# CDC_Amp_v31.net
KiCad netlist of a schematic drawn in EAGLE
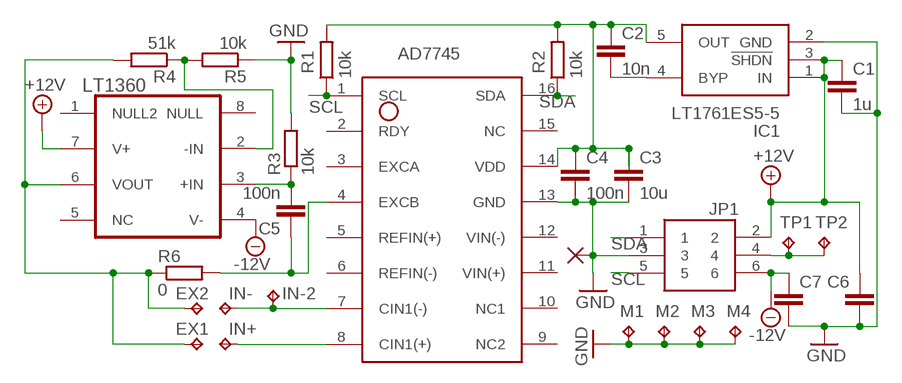
[diagram p0: schematic, sheet 1]

(export (version "E")
  (design (tool "Eeschema 10.0.6"))
  (components
    (comp (ref "AD7745")
      (value "AD7745")
      (footprint "eagle-import:AD7745_TSSOP_16")
      (libsource (lib "eagle-import") (part "AD7745_TSSOP_16"))
    )
    (comp (ref "C1")
      (value "1u")
      (footprint "eagle-import:RCL_C0805")
      (libsource (lib "eagle-import") (part "RCL_C-EUC0805"))
    )
    (comp (ref "C2")
      (value "10n")
      (footprint "eagle-import:RCL_C0805")
      (libsource (lib "eagle-import") (part "RCL_C-EUC0805"))
    )
    (comp (ref "C3")
      (value "10u")
      (footprint "eagle-import:RCL_C0805")
      (libsource (lib "eagle-import") (part "RCL_C-EUC0805"))
    )
    (comp (ref "C4")
      (value "100n")
      (footprint "eagle-import:RCL_C0805")
      (libsource (lib "eagle-import") (part "RCL_C-EUC0805"))
    )
    (comp (ref "C5")
      (value "100n")
      (footprint "eagle-import:RCL_C0805")
      (libsource (lib "eagle-import") (part "RCL_C-EUC0805"))
    )
    (comp (ref "C6")
      (value "RCL_C-EUC1206")
      (footprint "eagle-import:RCL_C1206")
      (libsource (lib "eagle-import") (part "RCL_C-EUC1206"))
    )
    (comp (ref "C7")
      (value "RCL_C-EUC1206")
      (footprint "eagle-import:RCL_C1206")
      (libsource (lib "eagle-import") (part "RCL_C-EUC1206"))
    )
    (comp (ref "EX1")
      (value "TESTPAD_TPTP15R")
      (footprint "eagle-import:TESTPAD_TP15R")
      (libsource (lib "eagle-import") (part "TESTPAD_TPTP15R"))
    )
    (comp (ref "EX2")
      (value "TESTPAD_TPTP15R")
      (footprint "eagle-import:TESTPAD_TP15R")
      (libsource (lib "eagle-import") (part "TESTPAD_TPTP15R"))
    )
    (comp (ref "GND")
      (value "WIREPAD_1,6/0,8")
      (footprint "eagle-import:WIREPAD_1,6_0,8")
      (libsource (lib "eagle-import") (part "WIREPAD_1,6/0,8"))
    )
    (comp (ref "IC1")
      (value "LT1761ES5-5")
      (footprint "eagle-import:SAMACSYS_PARTS_SOT95P280X100-5N")
      (fields
        (field (name "MANUFACTURER_PART_NUMBER") "LT1761ES5-3.3#TRMPBF")
        (field (name "MOUSER_PART_NUMBER") "584-1761ES5-3.3TMPF")
      )
      (libsource (lib "eagle-import") (part "SAMACSYS_PARTS_LT1761ES5-5#TRMPBF"))
    )
    (comp (ref "IN+")
      (value "TESTPAD_TPTP12R")
      (footprint "eagle-import:TESTPAD_TP12R")
      (libsource (lib "eagle-import") (part "TESTPAD_TPTP12R"))
    )
    (comp (ref "IN-")
      (value "TESTPAD_TPTP12R")
      (footprint "eagle-import:TESTPAD_TP12R")
      (libsource (lib "eagle-import") (part "TESTPAD_TPTP12R"))
    )
    (comp (ref "IN-2")
      (value "TESTPAD_TPTP12R")
      (footprint "eagle-import:TESTPAD_TP12R")
      (libsource (lib "eagle-import") (part "TESTPAD_TPTP12R"))
    )
    (comp (ref "JP1")
      (value "SAMACSYS_PARTS_FTSH-103-01-F-D")
      (footprint "eagle-import:SAMACSYS_PARTS_FTSH10301FD")
      (fields
        (field (name "MANUFACTURER_PART_NUMBER") "FTSH-103-01-F-D")
        (field (name "MOUSER_PART_NUMBER") "200-FTSH10301FD")
      )
      (libsource (lib "eagle-import") (part "SAMACSYS_PARTS_FTSH-103-01-F-D"))
    )
    (comp (ref "LT1360")
      (value "LT1360CS8PBF")
      (footprint "eagle-import:SO8")
      (fields (field (name "MPN") "LT1360CS8#PBF"))
      (libsource (lib "eagle-import") (part "LT1360CS8PBF"))
    )
    (comp (ref "M1")
      (value "TESTPAD_TPTP15R")
      (footprint "eagle-import:TESTPAD_TP15R")
      (libsource (lib "eagle-import") (part "TESTPAD_TPTP15R"))
    )
    (comp (ref "M2")
      (value "TESTPAD_TPTP15R")
      (footprint "eagle-import:TESTPAD_TP15R")
      (libsource (lib "eagle-import") (part "TESTPAD_TPTP15R"))
    )
    (comp (ref "M3")
      (value "TESTPAD_TPTP15R")
      (footprint "eagle-import:TESTPAD_TP15R")
      (libsource (lib "eagle-import") (part "TESTPAD_TPTP15R"))
    )
    (comp (ref "M4")
      (value "TESTPAD_TPTP15R")
      (footprint "eagle-import:TESTPAD_TP15R")
      (libsource (lib "eagle-import") (part "TESTPAD_TPTP15R"))
    )
    (comp (ref "R1")
      (value "10k")
      (footprint "eagle-import:RCL_R0805")
      (libsource (lib "eagle-import") (part "RCL_R-EU_R0805"))
    )
    (comp (ref "R2")
      (value "10k")
      (footprint "eagle-import:RCL_R0805")
      (libsource (lib "eagle-import") (part "RCL_R-EU_R0805"))
    )
    (comp (ref "R3")
      (value "10k")
      (footprint "eagle-import:RCL_R0805")
      (libsource (lib "eagle-import") (part "RCL_R-EU_R0805"))
    )
    (comp (ref "R4")
      (value "51k")
      (footprint "eagle-import:RCL_R0805")
      (libsource (lib "eagle-import") (part "RCL_R-EU_R0805"))
    )
    (comp (ref "R5")
      (value "10k")
      (footprint "eagle-import:RCL_R0805")
      (libsource (lib "eagle-import") (part "RCL_R-EU_R0805"))
    )
    (comp (ref "R6")
      (value "0")
      (footprint "eagle-import:RCL_R0603")
      (libsource (lib "eagle-import") (part "RCL_R-EU_R0603"))
    )
    (comp (ref "TP1")
      (value "TESTPAD_TPTP08SQ")
      (footprint "eagle-import:TESTPAD_TP08SQ")
      (libsource (lib "eagle-import") (part "TESTPAD_TPTP08SQ"))
    )
    (comp (ref "TP2")
      (value "TESTPAD_TPTP08SQ")
      (footprint "eagle-import:TESTPAD_TP08SQ")
      (libsource (lib "eagle-import") (part "TESTPAD_TPTP08SQ"))
    )
  )
  (nets
    (net (code "1") (name "+12V") (class "Default")
      (node (ref "C1") (pin "1") (pinfunction "1_1") (pintype "passive"))
      (node (ref "C6") (pin "1") (pinfunction "1_1") (pintype "passive"))
      (node (ref "IC1") (pin "1") (pinfunction "IN_1") (pintype "bidirectional"))
      (node (ref "IC1") (pin "3") (pinfunction "~{SHDN}_3") (pintype "bidirectional"))
      (node (ref "JP1") (pin "2") (pinfunction "2_2") (pintype "bidirectional"))
      (node (ref "LT1360") (pin "7") (pinfunction "V+_7") (pintype "power_in"))
    )
    (net (code "2") (name "-12V") (class "Default")
      (node (ref "C7") (pin "1") (pinfunction "1_1") (pintype "passive"))
      (node (ref "JP1") (pin "6") (pinfunction "6_6") (pintype "bidirectional"))
      (node (ref "LT1360") (pin "4") (pinfunction "V-_4") (pintype "power_in"))
    )
    (net (code "3") (name "/SCL") (class "Default")
      (node (ref "AD7745") (pin "1") (pinfunction "SCL_1") (pintype "bidirectional"))
      (node (ref "JP1") (pin "5") (pinfunction "5_5") (pintype "bidirectional"))
      (node (ref "R1") (pin "1") (pinfunction "1_1") (pintype "passive"))
    )
    (net (code "4") (name "/SDA") (class "Default")
      (node (ref "AD7745") (pin "16") (pinfunction "SDA_16") (pintype "bidirectional"))
      (node (ref "JP1") (pin "1") (pinfunction "1_1") (pintype "bidirectional"))
      (node (ref "R2") (pin "1") (pinfunction "1_1") (pintype "passive"))
    )
    (net (code "5") (name "GND") (class "Default")
      (node (ref "AD7745") (pin "13") (pinfunction "GND_13") (pintype "bidirectional"))
      (node (ref "C1") (pin "2") (pinfunction "2_2") (pintype "passive"))
      (node (ref "C3") (pin "2") (pinfunction "2_2") (pintype "passive"))
      (node (ref "C4") (pin "2") (pinfunction "2_2") (pintype "passive"))
      (node (ref "C6") (pin "2") (pinfunction "2_2") (pintype "passive"))
      (node (ref "C7") (pin "2") (pinfunction "2_2") (pintype "passive"))
      (node (ref "GND") (pin "1") (pinfunction "P_1") (pintype "passive"))
      (node (ref "IC1") (pin "2") (pinfunction "GND_2") (pintype "bidirectional"))
      (node (ref "JP1") (pin "3") (pinfunction "3_3") (pintype "bidirectional"))
      (node (ref "M1") (pin "TP") (pinfunction "TP_TP") (pintype "input"))
      (node (ref "M2") (pin "TP") (pinfunction "TP_TP") (pintype "input"))
      (node (ref "M3") (pin "TP") (pinfunction "TP_TP") (pintype "input"))
      (node (ref "M4") (pin "TP") (pinfunction "TP_TP") (pintype "input"))
      (node (ref "R3") (pin "2") (pinfunction "2_2") (pintype "passive"))
      (node (ref "R5") (pin "1") (pinfunction "1_1") (pintype "passive"))
    )
    (net (code "6") (name "Net-(AD7745-CIN1(+))") (class "Default")
      (node (ref "AD7745") (pin "8") (pinfunction "CIN1(+)_8") (pintype "bidirectional"))
      (node (ref "IN+") (pin "TP") (pinfunction "TP_TP") (pintype "input"))
    )
    (net (code "7") (name "Net-(AD7745-CIN1(-))") (class "Default")
      (node (ref "AD7745") (pin "7") (pinfunction "CIN1(-)_7") (pintype "bidirectional"))
      (node (ref "IN-") (pin "TP") (pinfunction "TP_TP") (pintype "input"))
      (node (ref "IN-2") (pin "TP") (pinfunction "TP_TP") (pintype "input"))
    )
    (net (code "8") (name "Net-(AD7745-EXCB)") (class "Default")
      (node (ref "AD7745") (pin "4") (pinfunction "EXCB_4") (pintype "bidirectional"))
      (node (ref "C5") (pin "1") (pinfunction "1_1") (pintype "passive"))
      (node (ref "R6") (pin "2") (pinfunction "2_2") (pintype "passive"))
    )
    (net (code "9") (name "Net-(AD7745-VDD)") (class "Default")
      (node (ref "AD7745") (pin "14") (pinfunction "VDD_14") (pintype "bidirectional"))
      (node (ref "C2") (pin "1") (pinfunction "1_1") (pintype "passive"))
      (node (ref "C3") (pin "1") (pinfunction "1_1") (pintype "passive"))
      (node (ref "C4") (pin "1") (pinfunction "1_1") (pintype "passive"))
      (node (ref "IC1") (pin "5") (pinfunction "OUT_5") (pintype "bidirectional"))
      (node (ref "R1") (pin "2") (pinfunction "2_2") (pintype "passive"))
      (node (ref "R2") (pin "2") (pinfunction "2_2") (pintype "passive"))
    )
    (net (code "10") (name "Net-(IC1-BYP)") (class "Default")
      (node (ref "C2") (pin "2") (pinfunction "2_2") (pintype "passive"))
      (node (ref "IC1") (pin "4") (pinfunction "BYP_4") (pintype "bidirectional"))
    )
    (net (code "11") (name "Net-(JP1-Pad4)") (class "Default")
      (node (ref "JP1") (pin "4") (pinfunction "4_4") (pintype "bidirectional"))
      (node (ref "TP1") (pin "TP") (pinfunction "TP_TP") (pintype "input"))
      (node (ref "TP2") (pin "TP") (pinfunction "TP_TP") (pintype "input"))
    )
    (net (code "12") (name "Net-(LT1360-+IN)") (class "Default")
      (node (ref "C5") (pin "2") (pinfunction "2_2") (pintype "passive"))
      (node (ref "LT1360") (pin "3") (pinfunction "+IN_3") (pintype "input"))
      (node (ref "R3") (pin "1") (pinfunction "1_1") (pintype "passive"))
    )
    (net (code "13") (name "Net-(LT1360--IN)") (class "Default")
      (node (ref "LT1360") (pin "2") (pinfunction "-IN_2") (pintype "input"))
      (node (ref "R4") (pin "1") (pinfunction "1_1") (pintype "passive"))
      (node (ref "R5") (pin "2") (pinfunction "2_2") (pintype "passive"))
    )
    (net (code "14") (name "Net-(LT1360-VOUT)") (class "Default")
      (node (ref "EX1") (pin "TP") (pinfunction "TP_TP") (pintype "input"))
      (node (ref "EX2") (pin "TP") (pinfunction "TP_TP") (pintype "input"))
      (node (ref "LT1360") (pin "6") (pinfunction "VOUT_6") (pintype "output"))
      (node (ref "R4") (pin "2") (pinfunction "2_2") (pintype "passive"))
      (node (ref "R6") (pin "1") (pinfunction "1_1") (pintype "passive"))
    )
    (net (code "15") (name "unconnected-(AD7745-EXCA-Pad3)") (class "Default")
      (node (ref "AD7745") (pin "3") (pinfunction "EXCA_3") (pintype "bidirectional"))
    )
    (net (code "16") (name "unconnected-(AD7745-NC-Pad15)") (class "Default")
      (node (ref "AD7745") (pin "15") (pinfunction "NC_15") (pintype "bidirectional"))
    )
    (net (code "17") (name "unconnected-(AD7745-NC1-Pad10)") (class "Default")
      (node (ref "AD7745") (pin "10") (pinfunction "NC1_10") (pintype "bidirectional"))
    )
    (net (code "18") (name "unconnected-(AD7745-NC2-Pad9)") (class "Default")
      (node (ref "AD7745") (pin "9") (pinfunction "NC2_9") (pintype "bidirectional"))
    )
    (net (code "19") (name "unconnected-(AD7745-RDY-Pad2)") (class "Default")
      (node (ref "AD7745") (pin "2") (pinfunction "RDY_2") (pintype "bidirectional"))
    )
    (net (code "20") (name "unconnected-(AD7745-REFIN(+)-Pad5)") (class "Default")
      (node (ref "AD7745") (pin "5") (pinfunction "REFIN(+)_5") (pintype "bidirectional"))
    )
    (net (code "21") (name "unconnected-(AD7745-REFIN(-)-Pad6)") (class "Default")
      (node (ref "AD7745") (pin "6") (pinfunction "REFIN(-)_6") (pintype "bidirectional"))
    )
    (net (code "22") (name "unconnected-(AD7745-VIN(+)-Pad11)") (class "Default")
      (node (ref "AD7745") (pin "11") (pinfunction "VIN(+)_11") (pintype "bidirectional"))
    )
    (net (code "23") (name "unconnected-(AD7745-VIN(-)-Pad12)") (class "Default")
      (node (ref "AD7745") (pin "12") (pinfunction "VIN(-)_12") (pintype "bidirectional"))
    )
    (net (code "24") (name "unconnected-(LT1360-NC-Pad5)") (class "Default")
      (node (ref "LT1360") (pin "5") (pinfunction "NC_5") (pintype "no_connect"))
    )
    (net (code "25") (name "unconnected-(LT1360-NULL-Pad8)") (class "Default")
      (node (ref "LT1360") (pin "8") (pinfunction "NULL_8") (pintype "passive"))
    )
    (net (code "26") (name "unconnected-(LT1360-NULL2-Pad1)") (class "Default")
      (node (ref "LT1360") (pin "1") (pinfunction "NULL2_1") (pintype "passive"))
    )
  )
)
